# led_svitilna.net
KiCad netlist of a schematic drawn in EAGLE
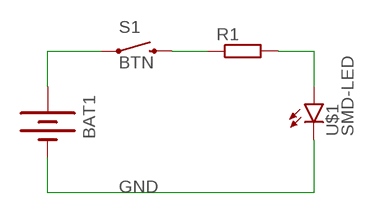
[diagram p0: schematic, sheet 1]

(export (version "E")
  (design (tool "Eeschema 10.0.6"))
  (components
    (comp (ref "BAT1")
      (value "BATTERY20SMD")
      (footprint "eagle-import:BATTCON_20MM")
      (libsource (lib "eagle-import") (part "BATTERY20SMD"))
    )
    (comp (ref "R1")
      (value "R-EU_R1206")
      (footprint "eagle-import:R1206")
      (libsource (lib "eagle-import") (part "R-EU_R1206"))
    )
    (comp (ref "S1")
      (value "BTN")
      (footprint "eagle-import:TACTILE_SWITCH_TALL")
      (libsource (lib "eagle-import") (part "SWITCH-MOMENTARY-2SMD-4"))
    )
    (comp (ref "U$1")
      (value "SMD-LED")
      (footprint "eagle-import:SMD-LED")
      (libsource (lib "eagle-import") (part "SMD-LED"))
    )
  )
  (nets
    (net (code "1") (name "/GND") (class "Default")
      (node (ref "BAT1") (pin "2") (pinfunction "-_2") (pintype "power_in"))
      (node (ref "U$1") (pin "K") (pinfunction "C_K") (pintype "passive"))
    )
    (net (code "2") (name "Net-(BAT1-+)") (class "Default")
      (node (ref "BAT1") (pin "1") (pinfunction "+_1") (pintype "power_in"))
      (node (ref "S1") (pin "A2") (pinfunction "1_A2") (pintype "passive"))
    )
    (net (code "3") (name "Net-(R1-Pad2)") (class "Default")
      (node (ref "R1") (pin "2") (pinfunction "2_2") (pintype "passive"))
      (node (ref "U$1") (pin "A") (pinfunction "A_A") (pintype "passive"))
    )
    (net (code "4") (name "Net-(S1-2)") (class "Default")
      (node (ref "R1") (pin "1") (pinfunction "1_1") (pintype "passive"))
      (node (ref "S1") (pin "B2") (pinfunction "2_B2") (pintype "passive"))
    )
  )
)
